# TMC4671.net
KiCad netlist of a schematic drawn in Altium Designer
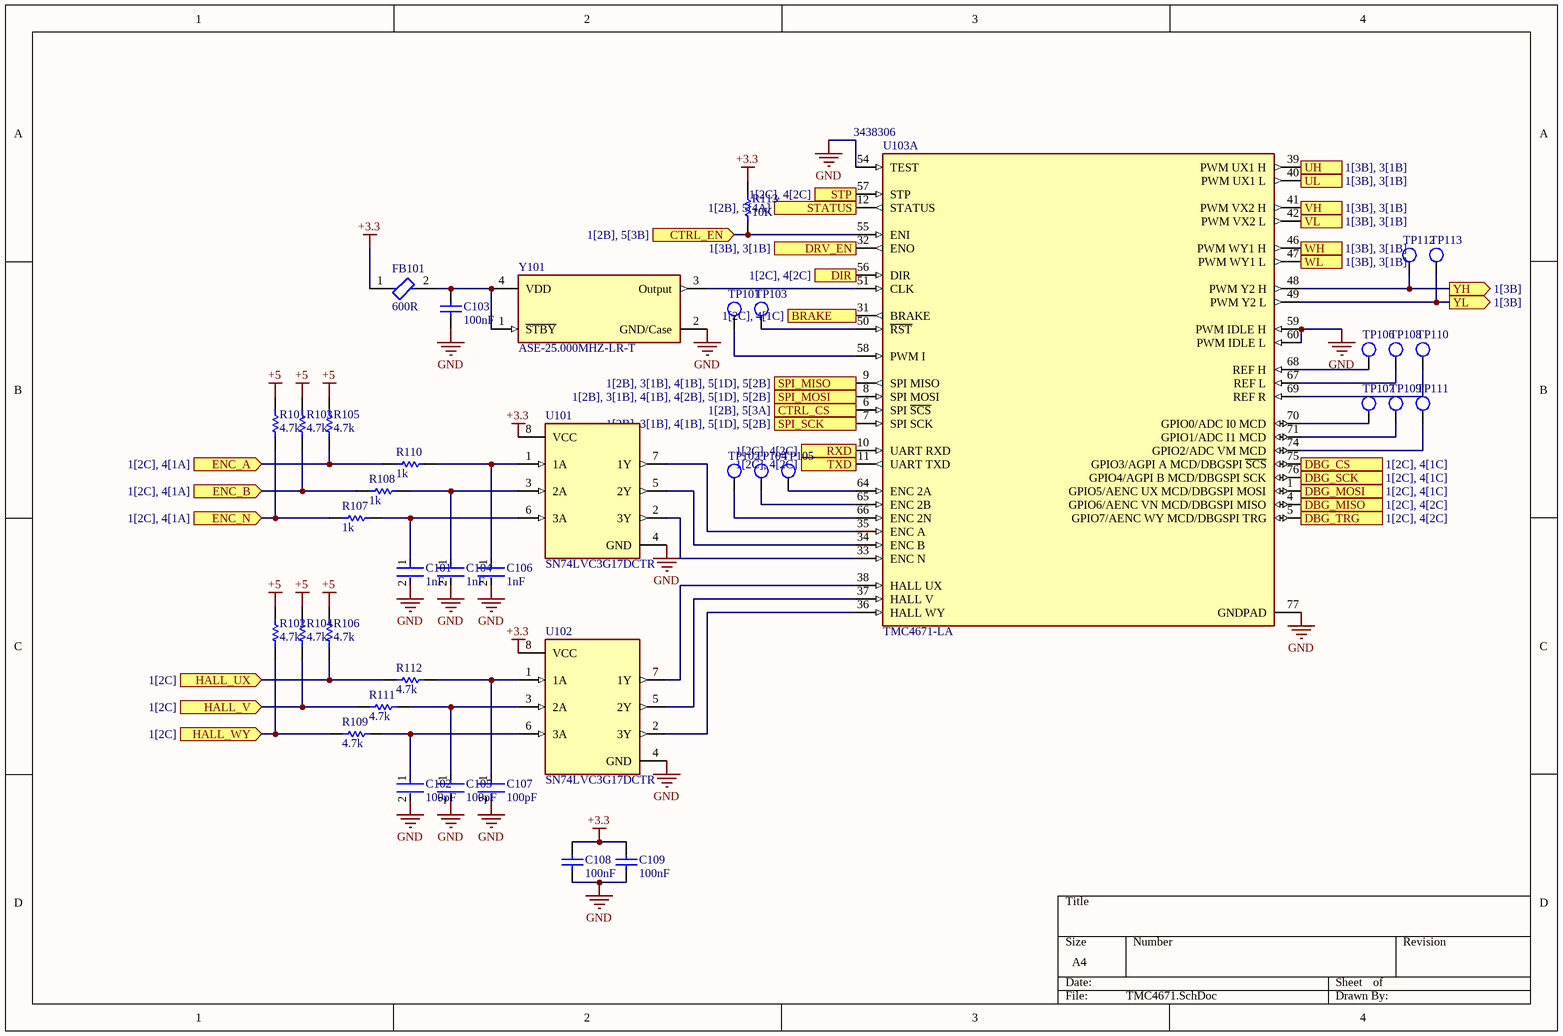
[diagram p0: TMC4671.SchDoc]

(export (version "E")
  (design (tool "Eeschema 10.0.6"))
  (components
    (comp (ref "C101")
      (value "1nF")
      (footprint "FP-C0603C-CF-MFG")
      (description "CAP CER 1000PF 100V 10% X7R 0603")
      (fields (field (name "TOLERANCE") "0.1") (field (name "MANUFACTURER") "KEMET"))
      (libsource (lib "Altium Content Vault") (part "b4654b650e69147ec39a6b967a45e02"))
    )
    (comp (ref "C102")
      (value "100pF")
      (footprint "FP-C0603C-CF-IPC_B")
      (description "CAP CER 100PF 50V 10% X7R 0603")
      (fields (field (name "MANUFACTURER") "KEMET") (field (name "TOLERANCE") "0.1"))
      (libsource (lib "Altium Content Vault") (part "b4654b650e69147ec39a6b967a45e02"))
    )
    (comp (ref "C103")
      (value "100nF")
      (footprint "CAPC1608X90X35NL10T15")
      (description "Chip Capacitor, 0.1 uF, +/- 10%, 50 V, -55 to 125 degC, 0603 (1608 Metric), RoHS, Tape and Reel")
      (fields (field (name "TOLERANCE") "10%") (field (name "VOLTAGE") "50V"))
      (libsource (lib "Altium Content Vault") (part "CAP-NP-2"))
    )
    (comp (ref "C104")
      (value "1nF")
      (footprint "FP-C0603C-CF-MFG")
      (description "CAP CER 1000PF 100V 10% X7R 0603")
      (fields (field (name "TOLERANCE") "0.1") (field (name "MANUFACTURER") "KEMET"))
      (libsource (lib "Altium Content Vault") (part "b4654b650e69147ec39a6b967a45e02"))
    )
    (comp (ref "C105")
      (value "100pF")
      (footprint "FP-C0603C-CF-IPC_B")
      (description "CAP CER 100PF 50V 10% X7R 0603")
      (fields (field (name "MANUFACTURER") "KEMET") (field (name "TOLERANCE") "0.1"))
      (libsource (lib "Altium Content Vault") (part "b4654b650e69147ec39a6b967a45e02"))
    )
    (comp (ref "C106")
      (value "1nF")
      (footprint "FP-C0603C-CF-MFG")
      (description "CAP CER 1000PF 100V 10% X7R 0603")
      (fields (field (name "TOLERANCE") "0.1") (field (name "MANUFACTURER") "KEMET"))
      (libsource (lib "Altium Content Vault") (part "b4654b650e69147ec39a6b967a45e02"))
    )
    (comp (ref "C107")
      (value "100pF")
      (footprint "FP-C0603C-CF-IPC_B")
      (description "CAP CER 100PF 50V 10% X7R 0603")
      (fields (field (name "MANUFACTURER") "KEMET") (field (name "TOLERANCE") "0.1"))
      (libsource (lib "Altium Content Vault") (part "b4654b650e69147ec39a6b967a45e02"))
    )
    (comp (ref "C108")
      (value "100nF")
      (footprint "CAPC1608X90X35NL10T15")
      (description "Chip Capacitor, 0.1 uF, +/- 10%, 50 V, -55 to 125 degC, 0603 (1608 Metric), RoHS, Tape and Reel")
      (fields (field (name "TOLERANCE") "10%") (field (name "VOLTAGE") "50V"))
      (libsource (lib "Altium Content Vault") (part "CAP-NP-2"))
    )
    (comp (ref "C109")
      (value "100nF")
      (footprint "CAPC1608X90X35NL10T15")
      (description "Chip Capacitor, 0.1 uF, +/- 10%, 50 V, -55 to 125 degC, 0603 (1608 Metric), RoHS, Tape and Reel")
      (fields (field (name "TOLERANCE") "10%") (field (name "VOLTAGE") "50V"))
      (libsource (lib "Altium Content Vault") (part "CAP-NP-2"))
    )
    (comp (ref "FB101")
      (value "600R")
      (footprint "FP-742792651-MFG")
      (description "FERRITE BEAD 600 OHM 0603 1LN")
      (fields (field (name "TOLERANCE") "25%"))
      (libsource (lib "Altium Content Vault") (part "5f30dd21d616792df468990f7003faa"))
    )
    (comp (ref "R101")
      (value "4.7k")
      (footprint "RESC1608X55X30NL15T15")
      (fields (field (name "TOLERANCE") "5%"))
      (libsource (lib "Altium Content Vault") (part "RES-2"))
    )
    (comp (ref "R102")
      (value "4.7k")
      (footprint "RESC1608X55X30NL15T15")
      (fields (field (name "TOLERANCE") "5%"))
      (libsource (lib "Altium Content Vault") (part "RES-2"))
    )
    (comp (ref "R103")
      (value "4.7k")
      (footprint "RESC1608X55X30NL15T15")
      (fields (field (name "TOLERANCE") "5%"))
      (libsource (lib "Altium Content Vault") (part "RES-2"))
    )
    (comp (ref "R104")
      (value "4.7k")
      (footprint "RESC1608X55X30NL15T15")
      (fields (field (name "TOLERANCE") "5%"))
      (libsource (lib "Altium Content Vault") (part "RES-2"))
    )
    (comp (ref "R105")
      (value "4.7k")
      (footprint "RESC1608X55X30NL15T15")
      (fields (field (name "TOLERANCE") "5%"))
      (libsource (lib "Altium Content Vault") (part "RES-2"))
    )
    (comp (ref "R106")
      (value "4.7k")
      (footprint "RESC1608X55X30NL15T15")
      (fields (field (name "TOLERANCE") "5%"))
      (libsource (lib "Altium Content Vault") (part "RES-2"))
    )
    (comp (ref "R107")
      (value "1k")
      (footprint "RESC1608X55X30ML15T15")
      (fields (field (name "PART NUMBER") "ERJ-3EKF1001V") (field (name "MANUFACTURER") "Panasonic"))
      (libsource (lib "Altium Content Vault") (part "RES"))
    )
    (comp (ref "R108")
      (value "1k")
      (footprint "RESC1608X55X30ML15T15")
      (fields (field (name "PART NUMBER") "ERJ-3EKF1001V") (field (name "MANUFACTURER") "Panasonic"))
      (libsource (lib "Altium Content Vault") (part "RES"))
    )
    (comp (ref "R109")
      (value "4.7k")
      (footprint "RESC1608X55X30NL15T15")
      (fields (field (name "TOLERANCE") "5%"))
      (libsource (lib "Altium Content Vault") (part "RES-2"))
    )
    (comp (ref "R110")
      (value "1k")
      (footprint "RESC1608X55X30ML15T15")
      (fields (field (name "PART NUMBER") "ERJ-3EKF1001V") (field (name "MANUFACTURER") "Panasonic"))
      (libsource (lib "Altium Content Vault") (part "RES"))
    )
    (comp (ref "R111")
      (value "4.7k")
      (footprint "RESC1608X55X30NL15T15")
      (fields (field (name "TOLERANCE") "5%"))
      (libsource (lib "Altium Content Vault") (part "RES-2"))
    )
    (comp (ref "R112")
      (value "4.7k")
      (footprint "RESC1608X55X30NL15T15")
      (fields (field (name "TOLERANCE") "5%"))
      (libsource (lib "Altium Content Vault") (part "RES-2"))
    )
    (comp (ref "R113")
      (value "10K")
      (footprint "RESC1609X55X30LL15T15")
      (description "Chip Resistor, 10 KOhm, +/- 1%, 0.1 W, -55 to 155 degC, 0603 (1608 Metric), RoHS, Tape and Reel")
      (fields (field (name "TOLERANCE") "1%") (field (name "MANUFACTURER") "Panasonic"))
      (libsource (lib "Altium Content Vault") (part "RES-2"))
    )
    (comp (ref "TP101")
      (value "TestPoint")
      (footprint "PCBComponent_1")
      (libsource (lib "Testpoint") (part "TestPoint"))
    )
    (comp (ref "TP102")
      (value "TestPoint")
      (footprint "PCBComponent_1")
      (libsource (lib "Testpoint") (part "TestPoint"))
    )
    (comp (ref "TP103")
      (value "TestPoint")
      (footprint "PCBComponent_1")
      (libsource (lib "Testpoint") (part "TestPoint"))
    )
    (comp (ref "TP104")
      (value "TestPoint")
      (footprint "PCBComponent_1")
      (libsource (lib "Testpoint") (part "TestPoint"))
    )
    (comp (ref "TP105")
      (value "TestPoint")
      (footprint "PCBComponent_1")
      (libsource (lib "Testpoint") (part "TestPoint"))
    )
    (comp (ref "TP106")
      (value "TestPoint")
      (footprint "PCBComponent_1")
      (libsource (lib "Testpoint") (part "TestPoint"))
    )
    (comp (ref "TP107")
      (value "TestPoint")
      (footprint "PCBComponent_1")
      (libsource (lib "Testpoint") (part "TestPoint"))
    )
    (comp (ref "TP108")
      (value "TestPoint")
      (footprint "PCBComponent_1")
      (libsource (lib "Testpoint") (part "TestPoint"))
    )
    (comp (ref "TP109")
      (value "TestPoint")
      (footprint "PCBComponent_1")
      (libsource (lib "Testpoint") (part "TestPoint"))
    )
    (comp (ref "TP110")
      (value "TestPoint")
      (footprint "PCBComponent_1")
      (libsource (lib "Testpoint") (part "TestPoint"))
    )
    (comp (ref "TP111")
      (value "TestPoint")
      (footprint "PCBComponent_1")
      (libsource (lib "Testpoint") (part "TestPoint"))
    )
    (comp (ref "TP112")
      (value "TestPoint")
      (footprint "PCBComponent_1")
      (libsource (lib "Testpoint") (part "TestPoint"))
    )
    (comp (ref "TP113")
      (value "TestPoint")
      (footprint "PCBComponent_1")
      (libsource (lib "Testpoint") (part "TestPoint"))
    )
    (comp (ref "U101")
      (value "SN74LVC3G17DCTR")
      (footprint "FP-DCT0008A-IPC_B")
      (description "IC BUFFER NON-INVERT 5.5V SM8")
      (fields
        (field (name "OCTOPART") "https://octopart.com/sn74lvc3g17dctr-texas+instruments-423176")
        (field (name "MANUFACTURER") "Texas Instruments")
      )
      (libsource (lib "Altium Content Vault") (part "5d02118b5b2f50f5f1f362055063dfe"))
    )
    (comp (ref "U102")
      (value "SN74LVC3G17DCTR")
      (footprint "FP-DCT0008A-IPC_B")
      (description "IC BUFFER NON-INVERT 5.5V SM8")
      (fields
        (field (name "OCTOPART") "https://octopart.com/sn74lvc3g17dctr-texas+instruments-423176")
        (field (name "MANUFACTURER") "Texas Instruments")
      )
      (libsource (lib "Altium Content Vault") (part "5d02118b5b2f50f5f1f362055063dfe"))
    )
    (comp (ref "U103")
      (value "TMC4671-LA")
      (footprint "FP-TMC4671-LA-IPC_A")
      (description "SERVO CONTROLLER IC, QFN76")
      (fields (field (name "SUPPLIER PART NUMBER 1") "3438306"))
      (libsource (lib "Altium Content Vault") (part "fddf9d8c5dbc63ee6fb3cd60f877672"))
    )
    (comp (ref "Y101")
      (value "ASE-25.000MHZ-LR-T")
      (footprint "FP-ASE-MFG")
      (description "XTAL Oscillator 25MHz ±25ppm CMOS 3.3V 4-SMD 3.2mm x 2.5mm")
      (libsource (lib "Altium Content Vault") (part "61a724e6190563596ac712fef61ad37"))
    )
  )
  (nets
    (net (code "1") (name "+3.3") (class "Default")
      (node (ref "C108") (pin "1") (pinfunction "1_1") (pintype "passive"))
      (node (ref "C109") (pin "1") (pinfunction "1_1") (pintype "passive"))
      (node (ref "FB101") (pin "1") (pinfunction "1_1") (pintype "passive"))
      (node (ref "R113") (pin "2") (pinfunction "2_2") (pintype "passive"))
      (node (ref "U101") (pin "8") (pinfunction "VCC_8") (pintype "power_in"))
      (node (ref "U102") (pin "8") (pinfunction "VCC_8") (pintype "power_in"))
    )
    (net (code "2") (name "+5") (class "Default")
      (node (ref "R101") (pin "2") (pinfunction "2_2") (pintype "passive"))
      (node (ref "R102") (pin "2") (pinfunction "2_2") (pintype "passive"))
      (node (ref "R103") (pin "2") (pinfunction "2_2") (pintype "passive"))
      (node (ref "R104") (pin "2") (pinfunction "2_2") (pintype "passive"))
      (node (ref "R105") (pin "2") (pinfunction "2_2") (pintype "passive"))
      (node (ref "R106") (pin "2") (pinfunction "2_2") (pintype "passive"))
    )
    (net (code "3") (name "/BRAKE") (class "Default")
      (node (ref "U103") (pin "31") (pinfunction "BRAKE_31") (pintype "output"))
    )
    (net (code "4") (name "/CTRL_CS") (class "Default")
      (node (ref "U103") (pin "6") (pinfunction "SPI_~{SCS}_6") (pintype "input"))
    )
    (net (code "5") (name "/CTRL_EN") (class "Default")
      (node (ref "R113") (pin "1") (pinfunction "1_1") (pintype "passive"))
      (node (ref "U103") (pin "55") (pinfunction "ENI_55") (pintype "input"))
    )
    (net (code "6") (name "/DBG_CS") (class "Default")
      (node (ref "U103") (pin "75") (pinfunction "GPIO3/AGPI_A_MCD/DBGSPI_~{SCS}_75") (pintype "bidirectional"))
    )
    (net (code "7") (name "/DBG_MISO") (class "Default")
      (node (ref "U103") (pin "4") (pinfunction "GPIO6/AENC_VN_MCD/DBGSPI_MISO_4") (pintype "bidirectional"))
    )
    (net (code "8") (name "/DBG_MOSI") (class "Default")
      (node (ref "U103") (pin "1") (pinfunction "GPIO5/AENC_UX_MCD/DBGSPI_MOSI_1") (pintype "bidirectional"))
    )
    (net (code "9") (name "/DBG_SCK") (class "Default")
      (node (ref "U103") (pin "76") (pinfunction "GPIO4/AGPI_B_MCD/DBGSPI_SCK_76") (pintype "bidirectional"))
    )
    (net (code "10") (name "/DBG_TRG") (class "Default")
      (node (ref "U103") (pin "5") (pinfunction "GPIO7/AENC_WY_MCD/DBGSPI_TRG_5") (pintype "bidirectional"))
    )
    (net (code "11") (name "/DIR") (class "Default")
      (node (ref "U103") (pin "56") (pinfunction "DIR_56") (pintype "input"))
    )
    (net (code "12") (name "/DRV_EN") (class "Default")
      (node (ref "U103") (pin "32") (pinfunction "ENO_32") (pintype "output"))
    )
    (net (code "13") (name "/ENC_A") (class "Default")
      (node (ref "R105") (pin "1") (pinfunction "1_1") (pintype "passive"))
      (node (ref "R110") (pin "1") (pinfunction "1_1") (pintype "passive"))
    )
    (net (code "14") (name "/ENC_B") (class "Default")
      (node (ref "R103") (pin "1") (pinfunction "1_1") (pintype "passive"))
      (node (ref "R108") (pin "1") (pinfunction "1_1") (pintype "passive"))
    )
    (net (code "15") (name "/ENC_N") (class "Default")
      (node (ref "R101") (pin "1") (pinfunction "1_1") (pintype "passive"))
      (node (ref "R107") (pin "1") (pinfunction "1_1") (pintype "passive"))
    )
    (net (code "16") (name "/HALL_UX") (class "Default")
      (node (ref "R106") (pin "1") (pinfunction "1_1") (pintype "passive"))
      (node (ref "R112") (pin "2") (pinfunction "2_2") (pintype "passive"))
    )
    (net (code "17") (name "/HALL_V") (class "Default")
      (node (ref "R104") (pin "1") (pinfunction "1_1") (pintype "passive"))
      (node (ref "R111") (pin "2") (pinfunction "2_2") (pintype "passive"))
    )
    (net (code "18") (name "/HALL_WY") (class "Default")
      (node (ref "R102") (pin "1") (pinfunction "1_1") (pintype "passive"))
      (node (ref "R109") (pin "2") (pinfunction "2_2") (pintype "passive"))
    )
    (net (code "19") (name "/RXD") (class "Default")
      (node (ref "U103") (pin "10") (pinfunction "UART_RXD_10") (pintype "input"))
    )
    (net (code "20") (name "/SPI_MISO") (class "Default")
      (node (ref "U103") (pin "9") (pinfunction "SPI_MISO_9") (pintype "output"))
    )
    (net (code "21") (name "/SPI_MOSI") (class "Default")
      (node (ref "U103") (pin "8") (pinfunction "SPI_MOSI_8") (pintype "input"))
    )
    (net (code "22") (name "/SPI_SCK") (class "Default")
      (node (ref "U103") (pin "7") (pinfunction "SPI_SCK_7") (pintype "input"))
    )
    (net (code "23") (name "/STATUS") (class "Default")
      (node (ref "U103") (pin "12") (pinfunction "STATUS_12") (pintype "output"))
    )
    (net (code "24") (name "/STP") (class "Default")
      (node (ref "U103") (pin "57") (pinfunction "STP_57") (pintype "input"))
    )
    (net (code "25") (name "/TXD") (class "Default")
      (node (ref "U103") (pin "11") (pinfunction "UART_TXD_11") (pintype "output"))
    )
    (net (code "26") (name "/UH") (class "Default")
      (node (ref "U103") (pin "39") (pinfunction "PWM_UX1_H_39") (pintype "output"))
    )
    (net (code "27") (name "/UL") (class "Default")
      (node (ref "U103") (pin "40") (pinfunction "PWM_UX1_L_40") (pintype "output"))
    )
    (net (code "28") (name "/VH") (class "Default")
      (node (ref "U103") (pin "41") (pinfunction "PWM_VX2_H_41") (pintype "output"))
    )
    (net (code "29") (name "/VL") (class "Default")
      (node (ref "U103") (pin "42") (pinfunction "PWM_VX2_L_42") (pintype "output"))
    )
    (net (code "30") (name "/WH") (class "Default")
      (node (ref "U103") (pin "46") (pinfunction "PWM_WY1_H_46") (pintype "output"))
    )
    (net (code "31") (name "/WL") (class "Default")
      (node (ref "U103") (pin "47") (pinfunction "PWM_WY1_L_47") (pintype "output"))
    )
    (net (code "32") (name "/YH") (class "Default")
      (node (ref "TP112") (pin "1") (pinfunction "1_1") (pintype "passive"))
      (node (ref "U103") (pin "48") (pinfunction "PWM_Y2_H_48") (pintype "output"))
    )
    (net (code "33") (name "/YL") (class "Default")
      (node (ref "TP113") (pin "1") (pinfunction "1_1") (pintype "passive"))
      (node (ref "U103") (pin "49") (pinfunction "PWM_Y2_L_49") (pintype "output"))
    )
    (net (code "34") (name "GND") (class "Default")
      (node (ref "C101") (pin "2") (pinfunction "2_2") (pintype "passive"))
      (node (ref "C102") (pin "2") (pinfunction "2_2") (pintype "passive"))
      (node (ref "C103") (pin "2") (pinfunction "2_2") (pintype "passive"))
      (node (ref "C104") (pin "2") (pinfunction "2_2") (pintype "passive"))
      (node (ref "C105") (pin "2") (pinfunction "2_2") (pintype "passive"))
      (node (ref "C106") (pin "2") (pinfunction "2_2") (pintype "passive"))
      (node (ref "C107") (pin "2") (pinfunction "2_2") (pintype "passive"))
      (node (ref "C108") (pin "2") (pinfunction "2_2") (pintype "passive"))
      (node (ref "C109") (pin "2") (pinfunction "2_2") (pintype "passive"))
      (node (ref "U101") (pin "4") (pinfunction "GND_4") (pintype "power_in"))
      (node (ref "U102") (pin "4") (pinfunction "GND_4") (pintype "power_in"))
      (node (ref "U103") (pin "54") (pinfunction "TEST_54") (pintype "input"))
      (node (ref "U103") (pin "59") (pinfunction "PWM_IDLE_H_59") (pintype "input"))
      (node (ref "U103") (pin "60") (pinfunction "PWM_IDLE_L_60") (pintype "input"))
      (node (ref "U103") (pin "77") (pinfunction "GNDPAD_77") (pintype "power_in"))
      (node (ref "Y101") (pin "2") (pinfunction "GND/Case_2") (pintype "power_in"))
    )
    (net (code "35") (name "Net-(U101-1A)") (class "Default")
      (node (ref "C106") (pin "1") (pinfunction "1_1") (pintype "passive"))
      (node (ref "R110") (pin "2") (pinfunction "2_2") (pintype "passive"))
      (node (ref "U101") (pin "1") (pinfunction "1A_1") (pintype "input"))
    )
    (net (code "36") (name "Net-(U101-1Y)") (class "Default")
      (node (ref "U101") (pin "7") (pinfunction "1Y_7") (pintype "output"))
      (node (ref "U103") (pin "35") (pinfunction "ENC_A_35") (pintype "input"))
    )
    (net (code "37") (name "Net-(U101-2A)") (class "Default")
      (node (ref "C104") (pin "1") (pinfunction "1_1") (pintype "passive"))
      (node (ref "R108") (pin "2") (pinfunction "2_2") (pintype "passive"))
      (node (ref "U101") (pin "3") (pinfunction "2A_3") (pintype "input"))
    )
    (net (code "38") (name "Net-(U101-2Y)") (class "Default")
      (node (ref "U101") (pin "5") (pinfunction "2Y_5") (pintype "output"))
      (node (ref "U103") (pin "34") (pinfunction "ENC_B_34") (pintype "input"))
    )
    (net (code "39") (name "Net-(U101-3A)") (class "Default")
      (node (ref "C101") (pin "1") (pinfunction "1_1") (pintype "passive"))
      (node (ref "R107") (pin "2") (pinfunction "2_2") (pintype "passive"))
      (node (ref "U101") (pin "6") (pinfunction "3A_6") (pintype "input"))
    )
    (net (code "40") (name "Net-(U101-3Y)") (class "Default")
      (node (ref "U101") (pin "2") (pinfunction "3Y_2") (pintype "output"))
      (node (ref "U103") (pin "33") (pinfunction "ENC_N_33") (pintype "input"))
    )
    (net (code "41") (name "Net-(U102-1A)") (class "Default")
      (node (ref "C107") (pin "1") (pinfunction "1_1") (pintype "passive"))
      (node (ref "R112") (pin "1") (pinfunction "1_1") (pintype "passive"))
      (node (ref "U102") (pin "1") (pinfunction "1A_1") (pintype "input"))
    )
    (net (code "42") (name "Net-(U102-1Y)") (class "Default")
      (node (ref "U102") (pin "7") (pinfunction "1Y_7") (pintype "output"))
      (node (ref "U103") (pin "38") (pinfunction "HALL_UX_38") (pintype "input"))
    )
    (net (code "43") (name "Net-(U102-2A)") (class "Default")
      (node (ref "C105") (pin "1") (pinfunction "1_1") (pintype "passive"))
      (node (ref "R111") (pin "1") (pinfunction "1_1") (pintype "passive"))
      (node (ref "U102") (pin "3") (pinfunction "2A_3") (pintype "input"))
    )
    (net (code "44") (name "Net-(U102-2Y)") (class "Default")
      (node (ref "U102") (pin "5") (pinfunction "2Y_5") (pintype "output"))
      (node (ref "U103") (pin "37") (pinfunction "HALL_V_37") (pintype "input"))
    )
    (net (code "45") (name "Net-(U102-3A)") (class "Default")
      (node (ref "C102") (pin "1") (pinfunction "1_1") (pintype "passive"))
      (node (ref "R109") (pin "1") (pinfunction "1_1") (pintype "passive"))
      (node (ref "U102") (pin "6") (pinfunction "3A_6") (pintype "input"))
    )
    (net (code "46") (name "Net-(U102-3Y)") (class "Default")
      (node (ref "U102") (pin "2") (pinfunction "3Y_2") (pintype "output"))
      (node (ref "U103") (pin "36") (pinfunction "HALL_WY_36") (pintype "input"))
    )
    (net (code "47") (name "Net-(U103A-CLK)") (class "Default")
      (node (ref "U103") (pin "51") (pinfunction "CLK_51") (pintype "input"))
      (node (ref "Y101") (pin "3") (pinfunction "Output_3") (pintype "output"))
    )
    (net (code "48") (name "Net-(U103A-ENC_2A)") (class "Default")
      (node (ref "TP105") (pin "1") (pinfunction "1_1") (pintype "passive"))
      (node (ref "U103") (pin "64") (pinfunction "ENC_2A_64") (pintype "input"))
    )
    (net (code "49") (name "Net-(U103A-ENC_2B)") (class "Default")
      (node (ref "TP104") (pin "1") (pinfunction "1_1") (pintype "passive"))
      (node (ref "U103") (pin "65") (pinfunction "ENC_2B_65") (pintype "input"))
    )
    (net (code "50") (name "Net-(U103A-ENC_2N)") (class "Default")
      (node (ref "TP102") (pin "1") (pinfunction "1_1") (pintype "passive"))
      (node (ref "U103") (pin "66") (pinfunction "ENC_2N_66") (pintype "input"))
    )
    (net (code "51") (name "Net-(U103A-GPIO0{slash}ADC_I0_MCD)") (class "Default")
      (node (ref "TP107") (pin "1") (pinfunction "1_1") (pintype "passive"))
      (node (ref "U103") (pin "70") (pinfunction "GPIO0/ADC_I0_MCD_70") (pintype "bidirectional"))
    )
    (net (code "52") (name "Net-(U103A-GPIO1{slash}ADC_I1_MCD)") (class "Default")
      (node (ref "TP109") (pin "1") (pinfunction "1_1") (pintype "passive"))
      (node (ref "U103") (pin "71") (pinfunction "GPIO1/ADC_I1_MCD_71") (pintype "bidirectional"))
    )
    (net (code "53") (name "Net-(U103A-GPIO2{slash}ADC_VM_MCD)") (class "Default")
      (node (ref "TP111") (pin "1") (pinfunction "1_1") (pintype "passive"))
      (node (ref "U103") (pin "74") (pinfunction "GPIO2/ADC_VM_MCD_74") (pintype "bidirectional"))
    )
    (net (code "54") (name "Net-(U103A-PWM_I)") (class "Default")
      (node (ref "TP101") (pin "1") (pinfunction "1_1") (pintype "passive"))
      (node (ref "U103") (pin "58") (pinfunction "PWM_I_58") (pintype "input"))
    )
    (net (code "55") (name "Net-(U103A-REF_H)") (class "Default")
      (node (ref "TP106") (pin "1") (pinfunction "1_1") (pintype "passive"))
      (node (ref "U103") (pin "68") (pinfunction "REF_H_68") (pintype "input"))
    )
    (net (code "56") (name "Net-(U103A-REF_L)") (class "Default")
      (node (ref "TP108") (pin "1") (pinfunction "1_1") (pintype "passive"))
      (node (ref "U103") (pin "67") (pinfunction "REF_L_67") (pintype "input"))
    )
    (net (code "57") (name "Net-(U103A-REF_R)") (class "Default")
      (node (ref "TP110") (pin "1") (pinfunction "1_1") (pintype "passive"))
      (node (ref "U103") (pin "69") (pinfunction "REF_R_69") (pintype "input"))
    )
    (net (code "58") (name "Net-(U103A-~{RST})") (class "Default")
      (node (ref "TP103") (pin "1") (pinfunction "1_1") (pintype "passive"))
      (node (ref "U103") (pin "50") (pinfunction "~{RST}_50") (pintype "input"))
    )
    (net (code "59") (name "Net-(Y101-VDD)") (class "Default")
      (node (ref "C103") (pin "1") (pinfunction "1_1") (pintype "passive"))
      (node (ref "FB101") (pin "2") (pinfunction "2_2") (pintype "passive"))
      (node (ref "Y101") (pin "1") (pinfunction "~{STBY}_1") (pintype "input"))
      (node (ref "Y101") (pin "4") (pinfunction "VDD_4") (pintype "power_in"))
    )
  )
)
